# megashield_rs485.net
KiCad netlist of a schematic drawn in EAGLE
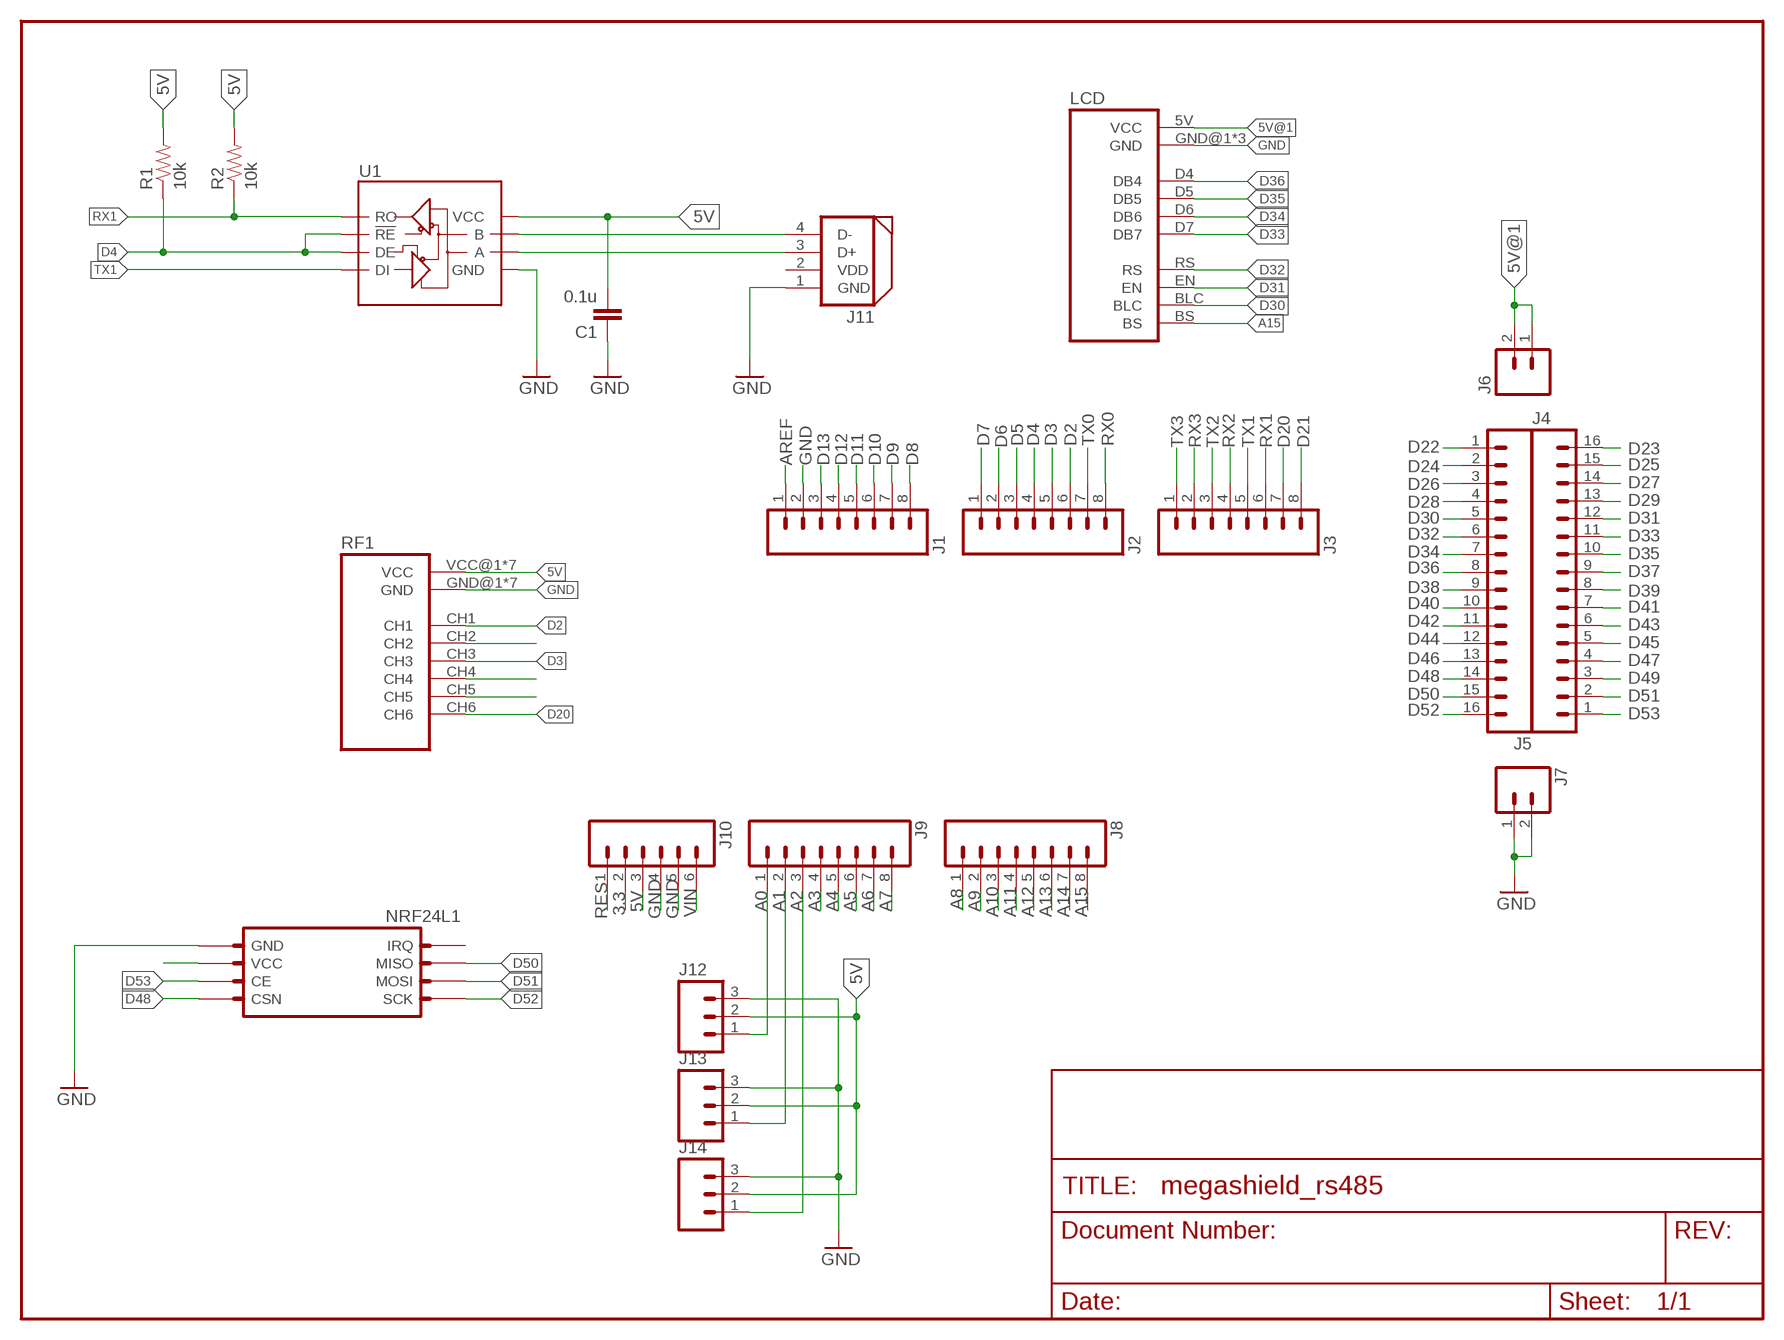
[diagram p0: schematic, sheet 1]

(export (version "E")
  (design (tool "Eeschema 10.0.6"))
  (components
    (comp (ref "C1")
      (value "0.1u")
      (footprint "eagle-import:CAP-PTH-SMALL")
      (libsource (lib "eagle-import") (part "CAPPTH"))
    )
    (comp (ref "J1")
      (value "M08LONGPADS")
      (footprint "eagle-import:1X08_LONGPADS")
      (libsource (lib "eagle-import") (part "M08LONGPADS"))
    )
    (comp (ref "J2")
      (value "M08LONGPADS")
      (footprint "eagle-import:1X08_LONGPADS")
      (libsource (lib "eagle-import") (part "M08LONGPADS"))
    )
    (comp (ref "J3")
      (value "M08LONGPADS")
      (footprint "eagle-import:1X08_LONGPADS")
      (libsource (lib "eagle-import") (part "M08LONGPADS"))
    )
    (comp (ref "J4")
      (value "M16PTH")
      (footprint "eagle-import:1X16")
      (libsource (lib "eagle-import") (part "M16PTH"))
    )
    (comp (ref "J5")
      (value "M16PTH")
      (footprint "eagle-import:1X16")
      (libsource (lib "eagle-import") (part "M16PTH"))
    )
    (comp (ref "J6")
      (value "M02PTH")
      (footprint "eagle-import:1X02")
      (libsource (lib "eagle-import") (part "M02PTH"))
    )
    (comp (ref "J7")
      (value "M02PTH")
      (footprint "eagle-import:1X02")
      (libsource (lib "eagle-import") (part "M02PTH"))
    )
    (comp (ref "J8")
      (value "M08LONGPADS")
      (footprint "eagle-import:1X08_LONGPADS")
      (libsource (lib "eagle-import") (part "M08LONGPADS"))
    )
    (comp (ref "J9")
      (value "M08LONGPADS")
      (footprint "eagle-import:1X08_LONGPADS")
      (libsource (lib "eagle-import") (part "M08LONGPADS"))
    )
    (comp (ref "J10")
      (value "M06LONGPADS")
      (footprint "eagle-import:1X06_LONGPADS")
      (libsource (lib "eagle-import") (part "M06LONGPADS"))
    )
    (comp (ref "J11")
      (value "DYNAMIXEL_RS485")
      (footprint "eagle-import:DYNAMIXEL_SPOX_04")
      (libsource (lib "eagle-import") (part "DYNAMIXEL_RS485"))
    )
    (comp (ref "J12")
      (value "M03PTH")
      (footprint "eagle-import:1X03")
      (libsource (lib "eagle-import") (part "M03PTH"))
    )
    (comp (ref "J13")
      (value "M03PTH")
      (footprint "eagle-import:1X03")
      (libsource (lib "eagle-import") (part "M03PTH"))
    )
    (comp (ref "J14")
      (value "M03PTH")
      (footprint "eagle-import:1X03")
      (libsource (lib "eagle-import") (part "M03PTH"))
    )
    (comp (ref "LCD")
      (value "LCD_SHIELD")
      (footprint "eagle-import:LCD_SHIELD")
      (libsource (lib "eagle-import") (part "LCD_SHIELD"))
    )
    (comp (ref "NRF24L1")
      (value "NRF")
      (footprint "eagle-import:NRF")
      (libsource (lib "eagle-import") (part "NRF"))
    )
    (comp (ref "R1")
      (value "10k")
      (footprint "eagle-import:AXIAL-0.4")
      (libsource (lib "eagle-import") (part "RESISTORPTH-1/4W"))
    )
    (comp (ref "R2")
      (value "10k")
      (footprint "eagle-import:AXIAL-0.4")
      (libsource (lib "eagle-import") (part "RESISTORPTH-1/4W"))
    )
    (comp (ref "RF1")
      (value "FS_R6B")
      (footprint "eagle-import:FS_R6B")
      (libsource (lib "eagle-import") (part "FS_R6B"))
    )
    (comp (ref "U1")
      (value "RS485")
      (footprint "eagle-import:DIL08")
      (libsource (lib "eagle-import") (part "SN75176B"))
    )
  )
  (nets
    (net (code "1") (name "/3.3") (class "Default")
      (node (ref "J10") (pin "2") (pinfunction "2_2") (pintype "passive"))
    )
    (net (code "2") (name "/A0") (class "Default")
      (node (ref "J12") (pin "1") (pinfunction "1_1") (pintype "passive"))
      (node (ref "J9") (pin "1") (pinfunction "1_1") (pintype "passive"))
    )
    (net (code "3") (name "/A1") (class "Default")
      (node (ref "J13") (pin "1") (pinfunction "1_1") (pintype "passive"))
      (node (ref "J9") (pin "2") (pinfunction "2_2") (pintype "passive"))
    )
    (net (code "4") (name "/A2") (class "Default")
      (node (ref "J14") (pin "1") (pinfunction "1_1") (pintype "passive"))
      (node (ref "J9") (pin "3") (pinfunction "3_3") (pintype "passive"))
    )
    (net (code "5") (name "/A3") (class "Default")
      (node (ref "J9") (pin "4") (pinfunction "4_4") (pintype "passive"))
    )
    (net (code "6") (name "/A4") (class "Default")
      (node (ref "J9") (pin "5") (pinfunction "5_5") (pintype "passive"))
    )
    (net (code "7") (name "/A5") (class "Default")
      (node (ref "J9") (pin "6") (pinfunction "6_6") (pintype "passive"))
    )
    (net (code "8") (name "/A6") (class "Default")
      (node (ref "J9") (pin "7") (pinfunction "7_7") (pintype "passive"))
    )
    (net (code "9") (name "/A7") (class "Default")
      (node (ref "J9") (pin "8") (pinfunction "8_8") (pintype "passive"))
    )
    (net (code "10") (name "/A8") (class "Default")
      (node (ref "J8") (pin "1") (pinfunction "1_1") (pintype "passive"))
    )
    (net (code "11") (name "/A9") (class "Default")
      (node (ref "J8") (pin "2") (pinfunction "2_2") (pintype "passive"))
    )
    (net (code "12") (name "/A10") (class "Default")
      (node (ref "J8") (pin "3") (pinfunction "3_3") (pintype "passive"))
    )
    (net (code "13") (name "/A11") (class "Default")
      (node (ref "J8") (pin "4") (pinfunction "4_4") (pintype "passive"))
    )
    (net (code "14") (name "/A12") (class "Default")
      (node (ref "J8") (pin "5") (pinfunction "5_5") (pintype "passive"))
    )
    (net (code "15") (name "/A13") (class "Default")
      (node (ref "J8") (pin "6") (pinfunction "6_6") (pintype "passive"))
    )
    (net (code "16") (name "/A14") (class "Default")
      (node (ref "J8") (pin "7") (pinfunction "7_7") (pintype "passive"))
    )
    (net (code "17") (name "/AREF") (class "Default")
      (node (ref "J1") (pin "1") (pinfunction "1_1") (pintype "passive"))
    )
    (net (code "18") (name "/D5") (class "Default")
      (node (ref "J2") (pin "3") (pinfunction "3_3") (pintype "passive"))
    )
    (net (code "19") (name "/D6") (class "Default")
      (node (ref "J2") (pin "2") (pinfunction "2_2") (pintype "passive"))
    )
    (net (code "20") (name "/D7") (class "Default")
      (node (ref "J2") (pin "1") (pinfunction "1_1") (pintype "passive"))
    )
    (net (code "21") (name "/D8") (class "Default")
      (node (ref "J1") (pin "8") (pinfunction "8_8") (pintype "passive"))
    )
    (net (code "22") (name "/D9") (class "Default")
      (node (ref "J1") (pin "7") (pinfunction "7_7") (pintype "passive"))
    )
    (net (code "23") (name "/D10") (class "Default")
      (node (ref "J1") (pin "6") (pinfunction "6_6") (pintype "passive"))
    )
    (net (code "24") (name "/D11") (class "Default")
      (node (ref "J1") (pin "5") (pinfunction "5_5") (pintype "passive"))
    )
    (net (code "25") (name "/D12") (class "Default")
      (node (ref "J1") (pin "4") (pinfunction "4_4") (pintype "passive"))
    )
    (net (code "26") (name "/D13") (class "Default")
      (node (ref "J1") (pin "3") (pinfunction "3_3") (pintype "passive"))
    )
    (net (code "27") (name "/D21") (class "Default")
      (node (ref "J3") (pin "8") (pinfunction "8_8") (pintype "passive"))
    )
    (net (code "28") (name "/D22") (class "Default")
      (node (ref "J5") (pin "1") (pinfunction "1_1") (pintype "passive"))
    )
    (net (code "29") (name "/D23") (class "Default")
      (node (ref "J4") (pin "16") (pinfunction "16_16") (pintype "passive"))
    )
    (net (code "30") (name "/D24") (class "Default")
      (node (ref "J5") (pin "2") (pinfunction "2_2") (pintype "passive"))
    )
    (net (code "31") (name "/D25") (class "Default")
      (node (ref "J4") (pin "15") (pinfunction "15_15") (pintype "passive"))
    )
    (net (code "32") (name "/D26") (class "Default")
      (node (ref "J5") (pin "3") (pinfunction "3_3") (pintype "passive"))
    )
    (net (code "33") (name "/D27") (class "Default")
      (node (ref "J4") (pin "14") (pinfunction "14_14") (pintype "passive"))
    )
    (net (code "34") (name "/D28") (class "Default")
      (node (ref "J5") (pin "4") (pinfunction "4_4") (pintype "passive"))
    )
    (net (code "35") (name "/D29") (class "Default")
      (node (ref "J4") (pin "13") (pinfunction "13_13") (pintype "passive"))
    )
    (net (code "36") (name "/D37") (class "Default")
      (node (ref "J4") (pin "9") (pinfunction "9_9") (pintype "passive"))
    )
    (net (code "37") (name "/D38") (class "Default")
      (node (ref "J5") (pin "9") (pinfunction "9_9") (pintype "passive"))
    )
    (net (code "38") (name "/D39") (class "Default")
      (node (ref "J4") (pin "8") (pinfunction "8_8") (pintype "passive"))
    )
    (net (code "39") (name "/D40") (class "Default")
      (node (ref "J5") (pin "10") (pinfunction "10_10") (pintype "passive"))
    )
    (net (code "40") (name "/D41") (class "Default")
      (node (ref "J4") (pin "7") (pinfunction "7_7") (pintype "passive"))
    )
    (net (code "41") (name "/D42") (class "Default")
      (node (ref "J5") (pin "11") (pinfunction "11_11") (pintype "passive"))
    )
    (net (code "42") (name "/D43") (class "Default")
      (node (ref "J4") (pin "6") (pinfunction "6_6") (pintype "passive"))
    )
    (net (code "43") (name "/D44") (class "Default")
      (node (ref "J5") (pin "12") (pinfunction "12_12") (pintype "passive"))
    )
    (net (code "44") (name "/D45") (class "Default")
      (node (ref "J4") (pin "5") (pinfunction "5_5") (pintype "passive"))
    )
    (net (code "45") (name "/D46") (class "Default")
      (node (ref "J5") (pin "13") (pinfunction "13_13") (pintype "passive"))
    )
    (net (code "46") (name "/D47") (class "Default")
      (node (ref "J4") (pin "4") (pinfunction "4_4") (pintype "passive"))
    )
    (net (code "47") (name "/D49") (class "Default")
      (node (ref "J4") (pin "3") (pinfunction "3_3") (pintype "passive"))
    )
    (net (code "48") (name "/RES") (class "Default")
      (node (ref "J10") (pin "1") (pinfunction "1_1") (pintype "passive"))
    )
    (net (code "49") (name "/RX0") (class "Default")
      (node (ref "J2") (pin "8") (pinfunction "8_8") (pintype "passive"))
    )
    (net (code "50") (name "/RX2") (class "Default")
      (node (ref "J3") (pin "4") (pinfunction "4_4") (pintype "passive"))
    )
    (net (code "51") (name "/RX3") (class "Default")
      (node (ref "J3") (pin "2") (pinfunction "2_2") (pintype "passive"))
    )
    (net (code "52") (name "/TX0") (class "Default")
      (node (ref "J2") (pin "7") (pinfunction "7_7") (pintype "passive"))
    )
    (net (code "53") (name "/TX2") (class "Default")
      (node (ref "J3") (pin "3") (pinfunction "3_3") (pintype "passive"))
    )
    (net (code "54") (name "/TX3") (class "Default")
      (node (ref "J3") (pin "1") (pinfunction "1_1") (pintype "passive"))
    )
    (net (code "55") (name "/VDD") (class "Default")
      (node (ref "J11") (pin "2") (pinfunction "VDD_2") (pintype "power_in"))
    )
    (net (code "56") (name "/VIN") (class "Default")
      (node (ref "J10") (pin "6") (pinfunction "6_6") (pintype "passive"))
    )
    (net (code "57") (name "5V") (class "Default")
      (node (ref "C1") (pin "2") (pinfunction "2_2") (pintype "passive"))
      (node (ref "J10") (pin "3") (pinfunction "3_3") (pintype "passive"))
      (node (ref "J12") (pin "2") (pinfunction "2_2") (pintype "passive"))
      (node (ref "J13") (pin "2") (pinfunction "2_2") (pintype "passive"))
      (node (ref "J14") (pin "2") (pinfunction "2_2") (pintype "passive"))
      (node (ref "R1") (pin "P$2") (pinfunction "2_P$2") (pintype "passive"))
      (node (ref "R2") (pin "P$2") (pinfunction "2_P$2") (pintype "passive"))
      (node (ref "RF1") (pin "VCC@1") (pinfunction "VCC_VCC@1") (pintype "power_in"))
      (node (ref "RF1") (pin "VCC@2") (pinfunction "VCC_VCC@2") (pintype "power_in"))
      (node (ref "RF1") (pin "VCC@3") (pinfunction "VCC_VCC@3") (pintype "power_in"))
      (node (ref "RF1") (pin "VCC@4") (pinfunction "VCC_VCC@4") (pintype "power_in"))
      (node (ref "RF1") (pin "VCC@5") (pinfunction "VCC_VCC@5") (pintype "power_in"))
      (node (ref "RF1") (pin "VCC@6") (pinfunction "VCC_VCC@6") (pintype "power_in"))
      (node (ref "RF1") (pin "VCC@7") (pinfunction "VCC_VCC@7") (pintype "power_in"))
      (node (ref "U1") (pin "8") (pinfunction "VCC_8") (pintype "bidirectional"))
    )
    (net (code "58") (name "5V@1") (class "Default")
      (node (ref "J6") (pin "1") (pinfunction "1_1") (pintype "passive"))
      (node (ref "J6") (pin "2") (pinfunction "2_2") (pintype "passive"))
      (node (ref "LCD") (pin "5V") (pinfunction "VCC_5V") (pintype "power_in"))
    )
    (net (code "59") (name "A15") (class "Default")
      (node (ref "J8") (pin "8") (pinfunction "8_8") (pintype "passive"))
      (node (ref "LCD") (pin "BS") (pinfunction "BS_BS") (pintype "output"))
    )
    (net (code "60") (name "D2") (class "Default")
      (node (ref "J2") (pin "6") (pinfunction "6_6") (pintype "passive"))
      (node (ref "RF1") (pin "CH1") (pinfunction "CH1_CH1") (pintype "output"))
    )
    (net (code "61") (name "D3") (class "Default")
      (node (ref "J2") (pin "5") (pinfunction "5_5") (pintype "passive"))
      (node (ref "RF1") (pin "CH3") (pinfunction "CH3_CH3") (pintype "output"))
    )
    (net (code "62") (name "D4") (class "Default")
      (node (ref "J2") (pin "4") (pinfunction "4_4") (pintype "passive"))
      (node (ref "R1") (pin "P$1") (pinfunction "1_P$1") (pintype "passive"))
      (node (ref "U1") (pin "2") (pinfunction "~{RE}_2") (pintype "bidirectional"))
      (node (ref "U1") (pin "3") (pinfunction "DE_3") (pintype "bidirectional"))
    )
    (net (code "63") (name "D20") (class "Default")
      (node (ref "J3") (pin "7") (pinfunction "7_7") (pintype "passive"))
      (node (ref "RF1") (pin "CH6") (pinfunction "CH6_CH6") (pintype "output"))
    )
    (net (code "64") (name "D30") (class "Default")
      (node (ref "J5") (pin "5") (pinfunction "5_5") (pintype "passive"))
      (node (ref "LCD") (pin "BLC") (pinfunction "BLC_BLC") (pintype "bidirectional"))
    )
    (net (code "65") (name "D31") (class "Default")
      (node (ref "J4") (pin "12") (pinfunction "12_12") (pintype "passive"))
      (node (ref "LCD") (pin "EN") (pinfunction "EN_EN") (pintype "bidirectional"))
    )
    (net (code "66") (name "D32") (class "Default")
      (node (ref "J5") (pin "6") (pinfunction "6_6") (pintype "passive"))
      (node (ref "LCD") (pin "RS") (pinfunction "RS_RS") (pintype "bidirectional"))
    )
    (net (code "67") (name "D33") (class "Default")
      (node (ref "J4") (pin "11") (pinfunction "11_11") (pintype "passive"))
      (node (ref "LCD") (pin "D7") (pinfunction "DB7_D7") (pintype "bidirectional"))
    )
    (net (code "68") (name "D34") (class "Default")
      (node (ref "J5") (pin "7") (pinfunction "7_7") (pintype "passive"))
      (node (ref "LCD") (pin "D6") (pinfunction "DB6_D6") (pintype "bidirectional"))
    )
    (net (code "69") (name "D35") (class "Default")
      (node (ref "J4") (pin "10") (pinfunction "10_10") (pintype "passive"))
      (node (ref "LCD") (pin "D5") (pinfunction "DB5_D5") (pintype "bidirectional"))
    )
    (net (code "70") (name "D36") (class "Default")
      (node (ref "J5") (pin "8") (pinfunction "8_8") (pintype "passive"))
      (node (ref "LCD") (pin "D4") (pinfunction "DB4_D4") (pintype "bidirectional"))
    )
    (net (code "71") (name "D48") (class "Default")
      (node (ref "J5") (pin "14") (pinfunction "14_14") (pintype "passive"))
      (node (ref "NRF24L1") (pin "4") (pinfunction "CSN_4") (pintype "bidirectional"))
    )
    (net (code "72") (name "D50") (class "Default")
      (node (ref "J5") (pin "15") (pinfunction "15_15") (pintype "passive"))
      (node (ref "NRF24L1") (pin "7") (pinfunction "MISO_7") (pintype "bidirectional"))
    )
    (net (code "73") (name "D51") (class "Default")
      (node (ref "J4") (pin "2") (pinfunction "2_2") (pintype "passive"))
      (node (ref "NRF24L1") (pin "6") (pinfunction "MOSI_6") (pintype "bidirectional"))
    )
    (net (code "74") (name "D52") (class "Default")
      (node (ref "J5") (pin "16") (pinfunction "16_16") (pintype "passive"))
      (node (ref "NRF24L1") (pin "5") (pinfunction "SCK_5") (pintype "bidirectional"))
    )
    (net (code "75") (name "D53") (class "Default")
      (node (ref "J4") (pin "1") (pinfunction "1_1") (pintype "passive"))
      (node (ref "NRF24L1") (pin "3") (pinfunction "CE_3") (pintype "bidirectional"))
    )
    (net (code "76") (name "GND") (class "Default")
      (node (ref "C1") (pin "1") (pinfunction "1_1") (pintype "passive"))
      (node (ref "J1") (pin "2") (pinfunction "2_2") (pintype "passive"))
      (node (ref "J10") (pin "4") (pinfunction "4_4") (pintype "passive"))
      (node (ref "J10") (pin "5") (pinfunction "5_5") (pintype "passive"))
      (node (ref "J11") (pin "1") (pinfunction "GND_1") (pintype "power_in"))
      (node (ref "J12") (pin "3") (pinfunction "3_3") (pintype "passive"))
      (node (ref "J13") (pin "3") (pinfunction "3_3") (pintype "passive"))
      (node (ref "J14") (pin "3") (pinfunction "3_3") (pintype "passive"))
      (node (ref "J7") (pin "1") (pinfunction "1_1") (pintype "passive"))
      (node (ref "J7") (pin "2") (pinfunction "2_2") (pintype "passive"))
      (node (ref "LCD") (pin "GND@1") (pinfunction "GND_GND@1") (pintype "power_in"))
      (node (ref "LCD") (pin "GND@2") (pinfunction "GND_GND@2") (pintype "power_in"))
      (node (ref "LCD") (pin "GND@3") (pinfunction "GND_GND@3") (pintype "power_in"))
      (node (ref "NRF24L1") (pin "P$1") (pinfunction "GND_P$1") (pintype "power_in"))
      (node (ref "RF1") (pin "GND@1") (pinfunction "GND_GND@1") (pintype "power_in"))
      (node (ref "RF1") (pin "GND@2") (pinfunction "GND_GND@2") (pintype "power_in"))
      (node (ref "RF1") (pin "GND@3") (pinfunction "GND_GND@3") (pintype "power_in"))
      (node (ref "RF1") (pin "GND@4") (pinfunction "GND_GND@4") (pintype "power_in"))
      (node (ref "RF1") (pin "GND@5") (pinfunction "GND_GND@5") (pintype "power_in"))
      (node (ref "RF1") (pin "GND@6") (pinfunction "GND_GND@6") (pintype "power_in"))
      (node (ref "RF1") (pin "GND@7") (pinfunction "GND_GND@7") (pintype "power_in"))
      (node (ref "U1") (pin "5") (pinfunction "GND_5") (pintype "bidirectional"))
    )
    (net (code "77") (name "Net-(J11-D+)") (class "Default")
      (node (ref "J11") (pin "3") (pinfunction "D+_3") (pintype "bidirectional"))
      (node (ref "U1") (pin "6") (pinfunction "A_6") (pintype "bidirectional"))
    )
    (net (code "78") (name "Net-(J11-D-)") (class "Default")
      (node (ref "J11") (pin "4") (pinfunction "D-_4") (pintype "bidirectional"))
      (node (ref "U1") (pin "7") (pinfunction "B_7") (pintype "bidirectional"))
    )
    (net (code "79") (name "RX1") (class "Default")
      (node (ref "J3") (pin "6") (pinfunction "6_6") (pintype "passive"))
      (node (ref "R2") (pin "P$1") (pinfunction "1_P$1") (pintype "passive"))
      (node (ref "U1") (pin "1") (pinfunction "RO_1") (pintype "bidirectional"))
    )
    (net (code "80") (name "TX1") (class "Default")
      (node (ref "J3") (pin "5") (pinfunction "5_5") (pintype "passive"))
      (node (ref "U1") (pin "4") (pinfunction "DI_4") (pintype "bidirectional"))
    )
    (net (code "81") (name "unconnected-(NRF24L1-IRQ-Pad8)") (class "Default")
      (node (ref "NRF24L1") (pin "8") (pinfunction "IRQ_8") (pintype "bidirectional"))
    )
    (net (code "82") (name "unconnected-(NRF24L1-VCC-Pad2)") (class "Default")
      (node (ref "NRF24L1") (pin "2") (pinfunction "VCC_2") (pintype "power_in"))
    )
    (net (code "83") (name "unconnected-(RF1-PadCH2)") (class "Default")
      (node (ref "RF1") (pin "CH2") (pinfunction "CH2_CH2") (pintype "output"))
    )
    (net (code "84") (name "unconnected-(RF1-PadCH4)") (class "Default")
      (node (ref "RF1") (pin "CH4") (pinfunction "CH4_CH4") (pintype "output"))
    )
    (net (code "85") (name "unconnected-(RF1-PadCH5)") (class "Default")
      (node (ref "RF1") (pin "CH5") (pinfunction "CH5_CH5") (pintype "output"))
    )
  )
)
